# motorLink.net
KiCad netlist of a schematic drawn in EAGLE
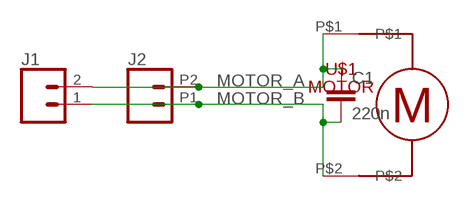
[diagram p0: schematic, sheet 1]

(export (version "E")
  (design (tool "Eeschema 10.0.6"))
  (components
    (comp (ref "C1")
      (value "220n")
      (footprint "eagle-import:1210")
      (libsource (lib "eagle-import") (part "CAP1210"))
    )
    (comp (ref "J1")
      (value "CONN_025MM")
      (footprint "eagle-import:SCREWTERMINAL-5MM-2")
      (libsource (lib "eagle-import") (part "CONN_025MM"))
    )
    (comp (ref "J2")
      (value "CONN_022.54MM_SCREWTERM")
      (footprint "eagle-import:1X02_2.54_SCREWTERM")
      (libsource (lib "eagle-import") (part "CONN_022.54MM_SCREWTERM"))
    )
    (comp (ref "U$1")
      (value "MOTOR")
      (footprint "eagle-import:MOTOR")
      (libsource (lib "eagle-import") (part "MOTOR"))
    )
  )
  (nets
    (net (code "1") (name "/MOTOR_A") (class "Default")
      (node (ref "C1") (pin "1") (pinfunction "1_1") (pintype "passive"))
      (node (ref "J1") (pin "2") (pinfunction "2_2") (pintype "passive"))
      (node (ref "J2") (pin "P2") (pinfunction "2_P2") (pintype "passive"))
      (node (ref "U$1") (pin "P$1") (pinfunction "P$1_P$1") (pintype "bidirectional"))
    )
    (net (code "2") (name "/MOTOR_B") (class "Default")
      (node (ref "C1") (pin "2") (pinfunction "2_2") (pintype "passive"))
      (node (ref "J1") (pin "1") (pinfunction "1_1") (pintype "passive"))
      (node (ref "J2") (pin "P1") (pinfunction "1_P1") (pintype "passive"))
      (node (ref "U$1") (pin "P$2") (pinfunction "P$2_P$2") (pintype "bidirectional"))
    )
  )
)
